# MCU0.net
KiCad netlist of a schematic drawn in Altium Designer
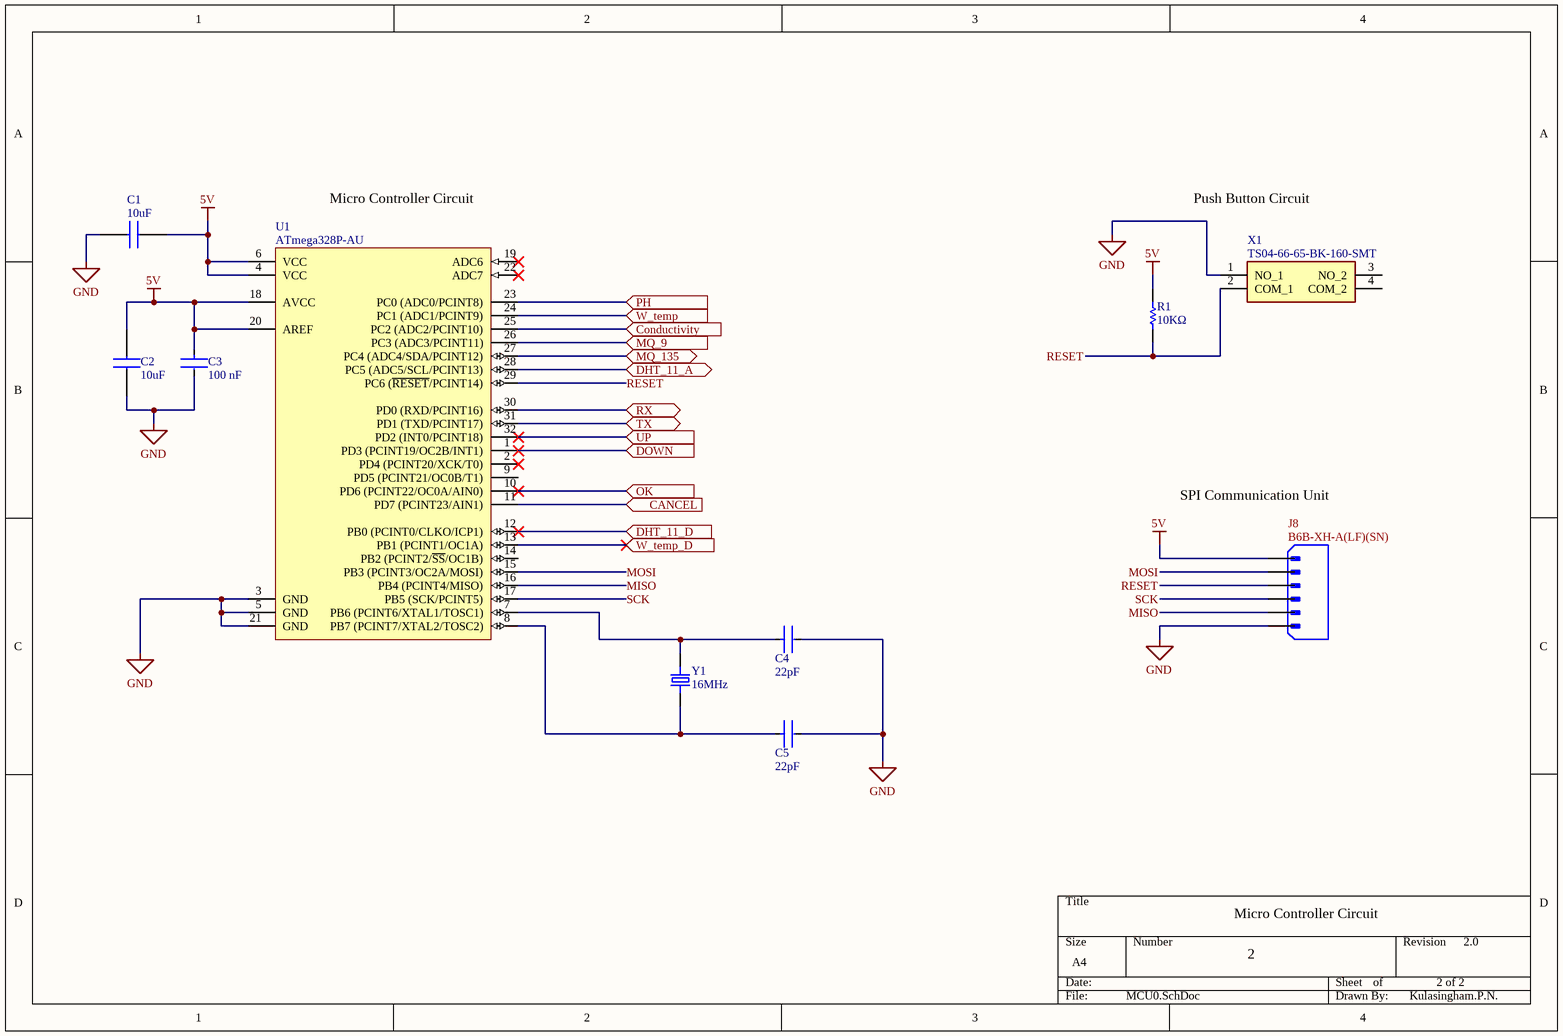
[diagram p0: MCU0.SchDoc]

(export (version "E")
  (design (tool "Eeschema 10.0.6"))
  (components
    (comp (ref "C1")
      (value "C1206C106K8RAC")
      (footprint "CAPC3216X180N")
      (description "Multilayer Ceramic Capacitors MLCC - SMD/SMT 10V 10uF X7R 1206 0.1")
      (fields (field (name "MOUSER PART NUMBER") "80-C1206C106K8RAC") (field (name "CAPACITANCE") "10uF"))
      (libsource (lib "EDR_New") (part "C1206C106K8RAC"))
    )
    (comp (ref "C2")
      (value "C1206C106K8RAC")
      (footprint "CAPC3216X180N")
      (description "Multilayer Ceramic Capacitors MLCC - SMD/SMT 10V 10uF X7R 1206 0.1")
      (fields (field (name "MOUSER PART NUMBER") "80-C1206C106K8RAC") (field (name "CAPACITANCE") "10uF"))
      (libsource (lib "EDR_New") (part "C1206C106K8RAC"))
    )
    (comp (ref "C3")
      (value "100 nF")
      (footprint "FP-CC1206-1_25-MFG")
      (description "CAP CER 0.1UF 50V X7R 1206")
      (fields
        (field (name "OCTOPART") "https://octopart.com/cc1206krx7r9bb104-yageo-39467816")
        (field (name "TOLERANCE") "0.1")
      )
      (libsource (lib "Altium Content Vault") (part "11868f565c42a9108669ba33697ecf6"))
    )
    (comp (ref "C4")
      (value "12065A220JAT2A")
      (footprint "FP-1206-L_3_2_0_2-W_1_6_0-IPC_C")
      (description "General Purpose Ceramic Capacitor, 1206, 22pF, 5%, NP0, 30ppm/°C, 50V")
      (fields
        (field (name "VOLTAGE") "50V")
        (field (name "TOLERANCE") "5%")
        (field (name "CAPACITANCE") "22pF")
      )
      (libsource (lib "Altium Content Vault") (part "02cd4be3c70576c341d710602a673aa"))
    )
    (comp (ref "C5")
      (value "12065A220JAT2A")
      (footprint "FP-1206-L_3_2_0_2-W_1_6_0-IPC_C")
      (description "General Purpose Ceramic Capacitor, 1206, 22pF, 5%, NP0, 30ppm/°C, 50V")
      (fields
        (field (name "VOLTAGE") "50V")
        (field (name "TOLERANCE") "5%")
        (field (name "CAPACITANCE") "22pF")
      )
      (libsource (lib "Altium Content Vault") (part "02cd4be3c70576c341d710602a673aa"))
    )
    (comp (ref "J8")
      (value "B6B-XH-A(LF)(SN)")
      (footprint "JST_B6B-XH-A(LF)(SN)")
      (description "Connector Header Through Hole 6 position 0.098 (2.50mm)")
      (fields (field (name "MF") "JST Sales"))
      (libsource (lib "EDR_New") (part "B6B-XH-A(LF)(SN)"))
    )
    (comp (ref "R1")
      (value "RC1206FR-0710KL")
      (footprint "RESC3116X65X40ML10T20")
      (description "Chip Resistor, 10 KOhm, +/- 1%, 0.25 W, -55 to 155 degC, 1206 (3216 Metric), RoHS, Tape and Reel")
      (fields
        (field (name "TOLERANCE") "1%")
        (field (name "RESISTANCE") "10KΩ")
        (field (name "MANUFACTURER") "Yageo")
      )
      (libsource (lib "Altium Content Vault") (part "RES-2"))
    )
    (comp (ref "U1")
      (value "ATmega328P-AU")
      (footprint "32A_L")
      (libsource (lib "Altium Content Vault") (part "MC-8B-ATM48-SQ32"))
    )
    (comp (ref "X1")
      (value "TS04-66-65-BK-160-SMT")
      (footprint "TS046665BK160SMT")
      (description "Tactile Switches 6 x 6 mm, 6.5 mm Act Height, 160 gf, Black, Surface Mount, SPST,")
      (fields (field (name "MOUSER PART NUMBER") "179-TS046665BK160SMT"))
      (libsource (lib "EDR_New") (part "TS04-66-65-BK-160-SMT"))
    )
    (comp (ref "Y1")
      (value "16MHz")
      (footprint "Oscillator")
      (fields (field (name "MP") "ECS-160-20-4") (field (name "Comment") "ECS-160-20-4_1"))
      (libsource (lib "EDR_New") (part "ECS-160-20-4_1"))
    )
  )
  (nets
    (net (code "1") (name "/CANCEL") (class "Default")
      (node (ref "U1") (pin "11") (pinfunction "PD7_(PCINT23/AIN1)_11") (pintype "passive"))
    )
    (net (code "2") (name "/Conductivity") (class "Default")
      (node (ref "U1") (pin "25") (pinfunction "PC2_(ADC2/PCINT10)_25") (pintype "passive"))
    )
    (net (code "3") (name "/DHT_11_A") (class "Default")
      (node (ref "U1") (pin "28") (pinfunction "PC5_(ADC5/SCL/PCINT13)_28") (pintype "bidirectional"))
    )
    (net (code "4") (name "/DHT_11_D") (class "Default")
      (node (ref "U1") (pin "12") (pinfunction "PB0_(PCINT0/CLKO/ICP1)_12") (pintype "bidirectional+no_connect"))
    )
    (net (code "5") (name "/DOWN") (class "Default")
      (node (ref "U1") (pin "1") (pinfunction "PD3_(PCINT19/OC2B/INT1)_1") (pintype "passive+no_connect"))
    )
    (net (code "6") (name "/MISO") (class "Default")
      (node (ref "J8") (pin "5") (pinfunction "5_5") (pintype "passive"))
      (node (ref "U1") (pin "16") (pinfunction "PB4_(PCINT4/MISO)_16") (pintype "bidirectional"))
    )
    (net (code "7") (name "/MOSI") (class "Default")
      (node (ref "J8") (pin "2") (pinfunction "2_2") (pintype "passive"))
      (node (ref "U1") (pin "15") (pinfunction "PB3_(PCINT3/OC2A/MOSI)_15") (pintype "bidirectional"))
    )
    (net (code "8") (name "/MQ_9") (class "Default")
      (node (ref "U1") (pin "26") (pinfunction "PC3_(ADC3/PCINT11)_26") (pintype "passive"))
    )
    (net (code "9") (name "/MQ_135") (class "Default")
      (node (ref "U1") (pin "27") (pinfunction "PC4_(ADC4/SDA/PCINT12)_27") (pintype "bidirectional"))
    )
    (net (code "10") (name "/OK") (class "Default")
      (node (ref "U1") (pin "10") (pinfunction "PD6_(PCINT22/OC0A/AIN0)_10") (pintype "passive+no_connect"))
    )
    (net (code "11") (name "/PH") (class "Default")
      (node (ref "U1") (pin "23") (pinfunction "PC0_(ADC0/PCINT8)_23") (pintype "passive"))
    )
    (net (code "12") (name "/RESET") (class "Default")
      (node (ref "J8") (pin "3") (pinfunction "3_3") (pintype "passive"))
      (node (ref "R1") (pin "1") (pinfunction "1_1") (pintype "passive"))
      (node (ref "U1") (pin "29") (pinfunction "PC6_(~{RESET}/PCINT14)_29") (pintype "bidirectional"))
      (node (ref "X1") (pin "2") (pinfunction "COM_1_2") (pintype "passive"))
    )
    (net (code "13") (name "/RX") (class "Default")
      (node (ref "U1") (pin "30") (pinfunction "PD0_(RXD/PCINT16)_30") (pintype "bidirectional"))
    )
    (net (code "14") (name "/SCK") (class "Default")
      (node (ref "J8") (pin "4") (pinfunction "4_4") (pintype "passive"))
      (node (ref "U1") (pin "17") (pinfunction "PB5_(SCK/PCINT5)_17") (pintype "bidirectional"))
    )
    (net (code "15") (name "/TX") (class "Default")
      (node (ref "U1") (pin "31") (pinfunction "PD1_(TXD/PCINT17)_31") (pintype "bidirectional"))
    )
    (net (code "16") (name "/UP") (class "Default")
      (node (ref "U1") (pin "32") (pinfunction "PD2_(INT0/PCINT18)_32") (pintype "passive+no_connect"))
    )
    (net (code "17") (name "/W_temp") (class "Default")
      (node (ref "U1") (pin "24") (pinfunction "PC1_(ADC1/PCINT9)_24") (pintype "passive"))
    )
    (net (code "18") (name "/W_temp_D") (class "Default")
      (node (ref "U1") (pin "13") (pinfunction "PB1_(PCINT1/OC1A)_13") (pintype "bidirectional+no_connect"))
    )
    (net (code "19") (name "5V") (class "Default")
      (node (ref "C1") (pin "2") (pinfunction "2_2") (pintype "passive"))
      (node (ref "C2") (pin "2") (pinfunction "2_2") (pintype "passive"))
      (node (ref "C3") (pin "1") (pinfunction "1_1") (pintype "passive"))
      (node (ref "J8") (pin "1") (pinfunction "M2_1") (pintype "passive"))
      (node (ref "R1") (pin "2") (pinfunction "2_2") (pintype "passive"))
      (node (ref "U1") (pin "18") (pinfunction "AVCC_18") (pintype "power_in"))
      (node (ref "U1") (pin "20") (pinfunction "AREF_20") (pintype "passive"))
      (node (ref "U1") (pin "4") (pinfunction "VCC_4") (pintype "power_in"))
      (node (ref "U1") (pin "6") (pinfunction "VCC_6") (pintype "power_in"))
    )
    (net (code "20") (name "GND") (class "Default")
      (node (ref "C1") (pin "1") (pinfunction "1_1") (pintype "passive"))
      (node (ref "C2") (pin "1") (pinfunction "1_1") (pintype "passive"))
      (node (ref "C3") (pin "2") (pinfunction "2_2") (pintype "passive"))
      (node (ref "C4") (pin "2") (pinfunction "2_2") (pintype "passive"))
      (node (ref "C5") (pin "2") (pinfunction "2_2") (pintype "passive"))
      (node (ref "J8") (pin "6") (pinfunction "M1_6") (pintype "passive"))
      (node (ref "U1") (pin "21") (pinfunction "GND_21") (pintype "power_in"))
      (node (ref "U1") (pin "3") (pinfunction "GND_3") (pintype "power_in"))
      (node (ref "U1") (pin "5") (pinfunction "GND_5") (pintype "power_in"))
      (node (ref "X1") (pin "1") (pinfunction "NO_1_1") (pintype "passive"))
    )
    (net (code "21") (name "Net-(U1-PB6_(PCINT6{slash}XTAL1{slash}TOSC1))") (class "Default")
      (node (ref "C4") (pin "1") (pinfunction "1_1") (pintype "passive"))
      (node (ref "U1") (pin "7") (pinfunction "PB6_(PCINT6/XTAL1/TOSC1)_7") (pintype "bidirectional"))
      (node (ref "Y1") (pin "2") (pinfunction "2_2") (pintype "passive"))
    )
    (net (code "22") (name "Net-(U1-PB7_(PCINT7{slash}XTAL2{slash}TOSC2))") (class "Default")
      (node (ref "C5") (pin "1") (pinfunction "1_1") (pintype "passive"))
      (node (ref "U1") (pin "8") (pinfunction "PB7_(PCINT7/XTAL2/TOSC2)_8") (pintype "bidirectional"))
      (node (ref "Y1") (pin "1") (pinfunction "1_1") (pintype "passive"))
    )
    (net (code "23") (name "unconnected-(U1-ADC6-Pad19)") (class "Default")
      (node (ref "U1") (pin "19") (pinfunction "ADC6_19") (pintype "input+no_connect"))
    )
    (net (code "24") (name "unconnected-(U1-ADC7-Pad22)") (class "Default")
      (node (ref "U1") (pin "22") (pinfunction "ADC7_22") (pintype "input+no_connect"))
    )
    (net (code "25") (name "unconnected-(U1-PB2_(PCINT2{slash}~{SS}{slash}OC1B)-Pad14)") (class "Default")
      (node (ref "U1") (pin "14") (pinfunction "PB2_(PCINT2/~{SS}/OC1B)_14") (pintype "bidirectional"))
    )
    (net (code "26") (name "unconnected-(U1-PD4_(PCINT20{slash}XCK{slash}T0)-Pad2)") (class "Default")
      (node (ref "U1") (pin "2") (pinfunction "PD4_(PCINT20/XCK/T0)_2") (pintype "passive+no_connect"))
    )
    (net (code "27") (name "unconnected-(U1-PD5_(PCINT21{slash}OC0B{slash}T1)-Pad9)") (class "Default")
      (node (ref "U1") (pin "9") (pinfunction "PD5_(PCINT21/OC0B/T1)_9") (pintype "passive"))
    )
    (net (code "28") (name "unconnected-(X1-COM_2-Pad4)") (class "Default")
      (node (ref "X1") (pin "4") (pinfunction "COM_2_4") (pintype "passive"))
    )
    (net (code "29") (name "unconnected-(X1-NO_2-Pad3)") (class "Default")
      (node (ref "X1") (pin "3") (pinfunction "NO_2_3") (pintype "passive"))
    )
  )
)
